# schematic.net
KiCad netlist of a schematic drawn in EAGLE
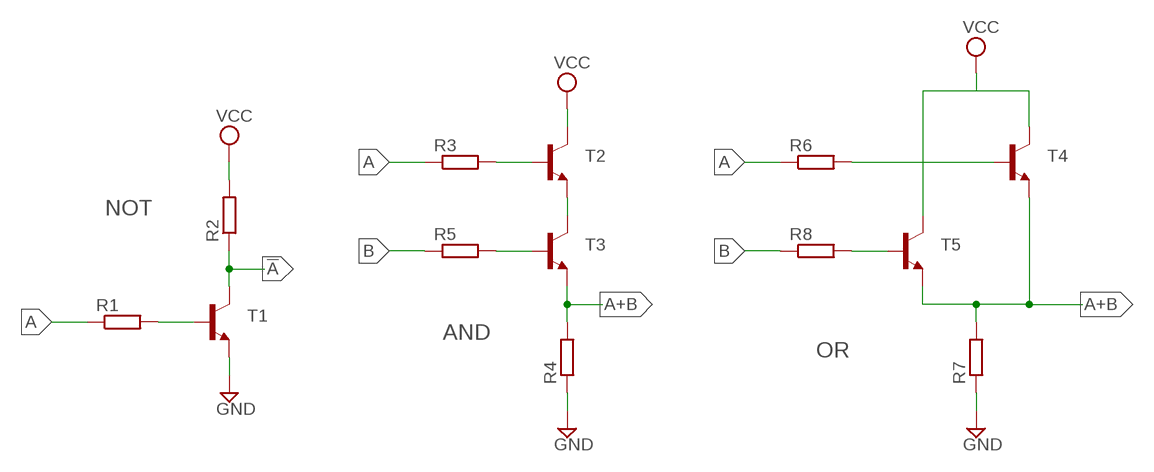
[diagram p0: schematic, sheet 1]

(export (version "E")
  (design (tool "Eeschema 10.0.6"))
  (components
    (comp (ref "R1")
      (value "R0204/7")
      (footprint "eagle-import:0204_7")
      (libsource (lib "eagle-import") (part "R0204/7"))
    )
    (comp (ref "R2")
      (value "R0204/7")
      (footprint "eagle-import:0204_7")
      (libsource (lib "eagle-import") (part "R0204/7"))
    )
    (comp (ref "R3")
      (value "R0204/7")
      (footprint "eagle-import:0204_7")
      (libsource (lib "eagle-import") (part "R0204/7"))
    )
    (comp (ref "R4")
      (value "R0204/7")
      (footprint "eagle-import:0204_7")
      (libsource (lib "eagle-import") (part "R0204/7"))
    )
    (comp (ref "R5")
      (value "R0204/7")
      (footprint "eagle-import:0204_7")
      (libsource (lib "eagle-import") (part "R0204/7"))
    )
    (comp (ref "R6")
      (value "R0204/7")
      (footprint "eagle-import:0204_7")
      (libsource (lib "eagle-import") (part "R0204/7"))
    )
    (comp (ref "R7")
      (value "R0204/7")
      (footprint "eagle-import:0204_7")
      (libsource (lib "eagle-import") (part "R0204/7"))
    )
    (comp (ref "R8")
      (value "R0204/7")
      (footprint "eagle-import:0204_7")
      (libsource (lib "eagle-import") (part "R0204/7"))
    )
    (comp (ref "T1")
      (value "2N3904")
      (footprint "eagle-import:TO92")
      (libsource (lib "eagle-import") (part "2N3904"))
    )
    (comp (ref "T2")
      (value "2N3904")
      (footprint "eagle-import:TO92")
      (libsource (lib "eagle-import") (part "2N3904"))
    )
    (comp (ref "T3")
      (value "2N3904")
      (footprint "eagle-import:TO92")
      (libsource (lib "eagle-import") (part "2N3904"))
    )
    (comp (ref "T4")
      (value "2N3904")
      (footprint "eagle-import:TO92")
      (libsource (lib "eagle-import") (part "2N3904"))
    )
    (comp (ref "T5")
      (value "2N3904")
      (footprint "eagle-import:TO92")
      (libsource (lib "eagle-import") (part "2N3904"))
    )
  )
  (nets
    (net (code "1") (name "/~{A}") (class "Default")
      (node (ref "R2") (pin "1") (pinfunction "1_1") (pintype "passive"))
      (node (ref "T1") (pin "1") (pinfunction "C_1") (pintype "passive"))
    )
    (net (code "2") (name "A") (class "Default")
      (node (ref "R1") (pin "1") (pinfunction "1_1") (pintype "passive"))
      (node (ref "R3") (pin "1") (pinfunction "1_1") (pintype "passive"))
      (node (ref "R6") (pin "1") (pinfunction "1_1") (pintype "passive"))
    )
    (net (code "3") (name "A+B") (class "Default")
      (node (ref "R4") (pin "2") (pinfunction "2_2") (pintype "passive"))
      (node (ref "R7") (pin "2") (pinfunction "2_2") (pintype "passive"))
      (node (ref "T3") (pin "3") (pinfunction "E_3") (pintype "passive"))
      (node (ref "T4") (pin "3") (pinfunction "E_3") (pintype "passive"))
      (node (ref "T5") (pin "3") (pinfunction "E_3") (pintype "passive"))
    )
    (net (code "4") (name "B") (class "Default")
      (node (ref "R5") (pin "1") (pinfunction "1_1") (pintype "passive"))
      (node (ref "R8") (pin "1") (pinfunction "1_1") (pintype "passive"))
    )
    (net (code "5") (name "GND") (class "Default")
      (node (ref "R4") (pin "1") (pinfunction "1_1") (pintype "passive"))
      (node (ref "R7") (pin "1") (pinfunction "1_1") (pintype "passive"))
      (node (ref "T1") (pin "3") (pinfunction "E_3") (pintype "passive"))
    )
    (net (code "6") (name "Net-(T1-B)") (class "Default")
      (node (ref "R1") (pin "2") (pinfunction "2_2") (pintype "passive"))
      (node (ref "T1") (pin "2") (pinfunction "B_2") (pintype "passive"))
    )
    (net (code "7") (name "Net-(T2-B)") (class "Default")
      (node (ref "R3") (pin "2") (pinfunction "2_2") (pintype "passive"))
      (node (ref "T2") (pin "2") (pinfunction "B_2") (pintype "passive"))
    )
    (net (code "8") (name "Net-(T2-E)") (class "Default")
      (node (ref "T2") (pin "3") (pinfunction "E_3") (pintype "passive"))
      (node (ref "T3") (pin "1") (pinfunction "C_1") (pintype "passive"))
    )
    (net (code "9") (name "Net-(T3-B)") (class "Default")
      (node (ref "R5") (pin "2") (pinfunction "2_2") (pintype "passive"))
      (node (ref "T3") (pin "2") (pinfunction "B_2") (pintype "passive"))
    )
    (net (code "10") (name "Net-(T4-B)") (class "Default")
      (node (ref "R6") (pin "2") (pinfunction "2_2") (pintype "passive"))
      (node (ref "T4") (pin "2") (pinfunction "B_2") (pintype "passive"))
    )
    (net (code "11") (name "Net-(T5-B)") (class "Default")
      (node (ref "R8") (pin "2") (pinfunction "2_2") (pintype "passive"))
      (node (ref "T5") (pin "2") (pinfunction "B_2") (pintype "passive"))
    )
    (net (code "12") (name "VCC") (class "Default")
      (node (ref "R2") (pin "2") (pinfunction "2_2") (pintype "passive"))
      (node (ref "T2") (pin "1") (pinfunction "C_1") (pintype "passive"))
      (node (ref "T4") (pin "1") (pinfunction "C_1") (pintype "passive"))
      (node (ref "T5") (pin "1") (pinfunction "C_1") (pintype "passive"))
    )
  )
)
